# Limit_Switches.net
KiCad netlist of a schematic drawn in Altium Designer
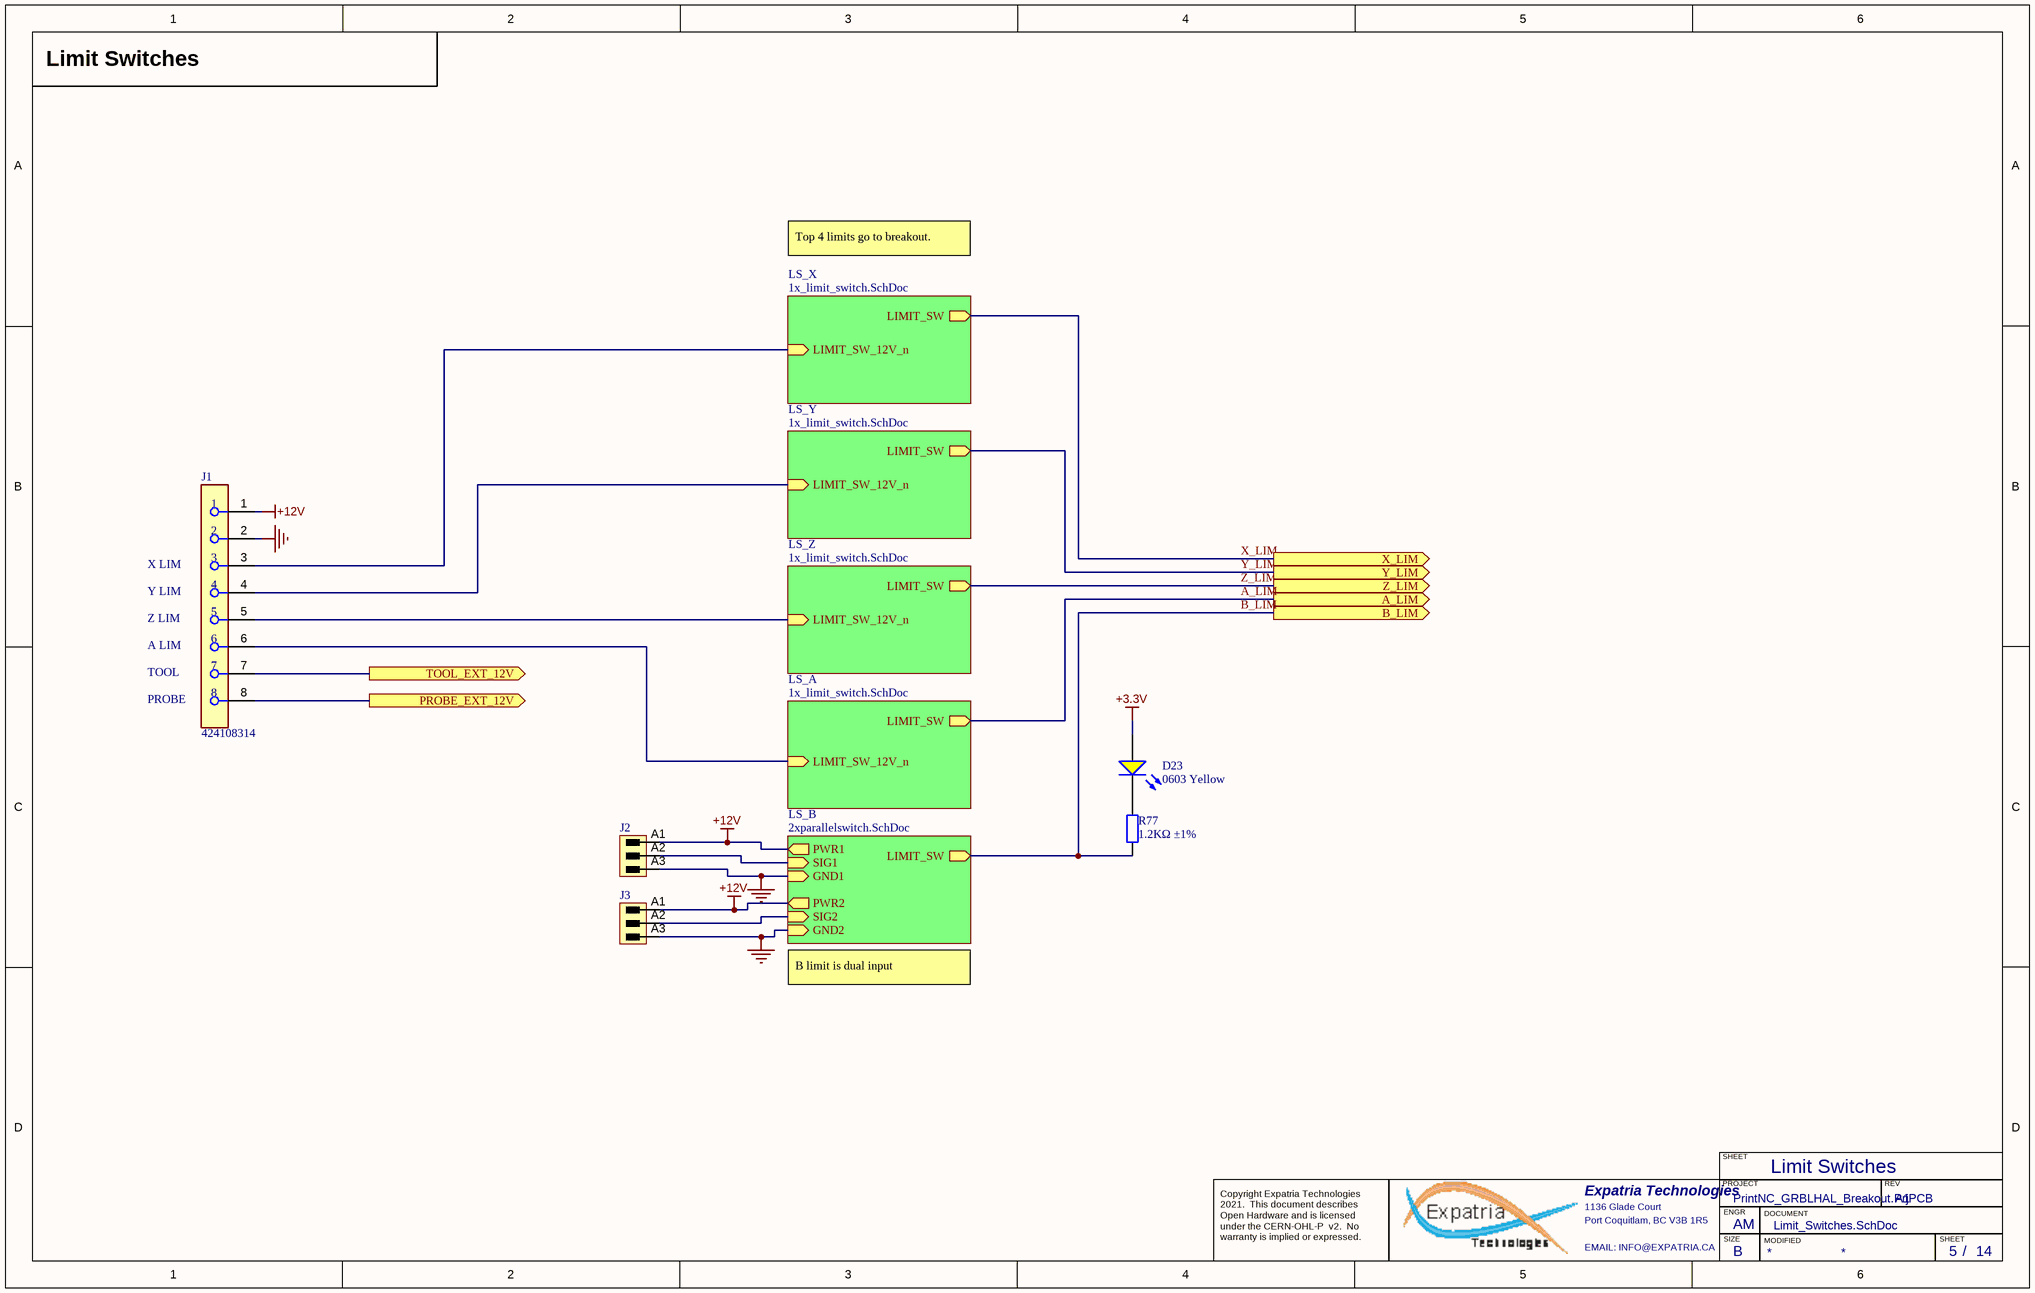
[diagram p0: Limit_Switches.SchDoc]

(export (version "E")
  (design (tool "Eeschema 10.0.6"))
  (components
    (comp (ref "D23")
      (value "0603 Yellow")
      (footprint "0603_LED_S1")
      (description "LED")
      (libsource (lib "LED") (part "0603 LED Yellow"))
    )
    (comp (ref "J1")
      (value "424108314")
      (footprint "FP-5555799-1-MFG")
      (description "CONN MOD JACK 8P8C VERT UNSHLD")
      (libsource (lib "PrintNC_GRBLHAL_Breakout") (part "a32a9c29f5c2290c50060dfb8ad7212"))
    )
    (comp (ref "J2")
      (value "~")
      (footprint "SL_3_50_180G_03")
      (fields
        (field (name "PARTNUMBER") "WJ15EDGVC-3.5-3P")
        (field (name "MANUFACTURER") "Ningbo Kangnex Elec")
      )
      (libsource (lib "PrintNC_GRBLHAL_Breakout") (part "Header_Male_03_1x03"))
    )
    (comp (ref "J3")
      (value "~")
      (footprint "SL_3_50_180G_03")
      (fields
        (field (name "PARTNUMBER") "WJ15EDGVC-3.5-3P")
        (field (name "MANUFACTURER") "Ningbo Kangnex Elec")
      )
      (libsource (lib "PrintNC_GRBLHAL_Breakout") (part "Header_Male_03_1x03"))
    )
    (comp (ref "R77")
      (value "1.2KΩ ±1%")
      (footprint "0402_R")
      (description "Chip resistor")
      (fields (field (name "MANUFACTURER") "Uniroyal Elec") (field (name "PARTNUMBER") "0402WGF1201TCE"))
      (libsource (lib "PrintNC_GRBLHAL_Breakout") (part "0402 1.2K (1201) 1%"))
    )
  )
  (nets
    (net (code "1") (name "+3.3V") (class "Default")
      (node (ref "D23") (pin "A") (pinfunction "A_A") (pintype "passive"))
    )
    (net (code "2") (name "+12V") (class "Default")
      (node (ref "J1") (pin "1") (pinfunction "1_1") (pintype "passive"))
      (node (ref "J2") (pin "A1") (pinfunction "A1_A1") (pintype "passive"))
      (node (ref "J3") (pin "A1") (pinfunction "A1_A1") (pintype "passive"))
    )
    (net (code "4") (name "/B_LIM") (class "Default")
      (node (ref "R77") (pin "1") (pinfunction "1_1") (pintype "passive"))
    )
    (net (code "5") (name "/LIMIT_SW_12V_n") (class "Default")
      (node (ref "J1") (pin "6") (pinfunction "6_6") (pintype "passive"))
    )
    (net (code "6") (name "/LIMIT_SW_12V_n_1") (class "Default")
      (node (ref "J1") (pin "3") (pinfunction "3_3") (pintype "passive"))
    )
    (net (code "7") (name "/LIMIT_SW_12V_n_2") (class "Default")
      (node (ref "J1") (pin "4") (pinfunction "4_4") (pintype "passive"))
    )
    (net (code "8") (name "/LIMIT_SW_12V_n_3") (class "Default")
      (node (ref "J1") (pin "5") (pinfunction "5_5") (pintype "passive"))
    )
    (net (code "9") (name "/PROBE_EXT_12V") (class "Default")
      (node (ref "J1") (pin "8") (pinfunction "8_8") (pintype "passive"))
    )
    (net (code "10") (name "/SIG1") (class "Default")
      (node (ref "J2") (pin "A2") (pinfunction "A2_A2") (pintype "passive"))
    )
    (net (code "11") (name "/SIG2") (class "Default")
      (node (ref "J3") (pin "A2") (pinfunction "A2_A2") (pintype "passive"))
    )
    (net (code "12") (name "/TOOL_EXT_12V") (class "Default")
      (node (ref "J1") (pin "7") (pinfunction "7_7") (pintype "passive"))
    )
    (net (code "16") (name "GND") (class "Default")
      (node (ref "J1") (pin "2") (pinfunction "2_2") (pintype "passive"))
      (node (ref "J2") (pin "A3") (pinfunction "A3_A3") (pintype "passive"))
      (node (ref "J3") (pin "A3") (pinfunction "A3_A3") (pintype "passive"))
    )
    (net (code "17") (name "Net-(D23-PadK)") (class "Default")
      (node (ref "D23") (pin "K") (pinfunction "K_K") (pintype "passive"))
      (node (ref "R77") (pin "2") (pinfunction "2_2") (pintype "passive"))
    )
  )
)
